# BNO055_Xplained_pro.net
KiCad netlist of a schematic drawn in Altium Designer
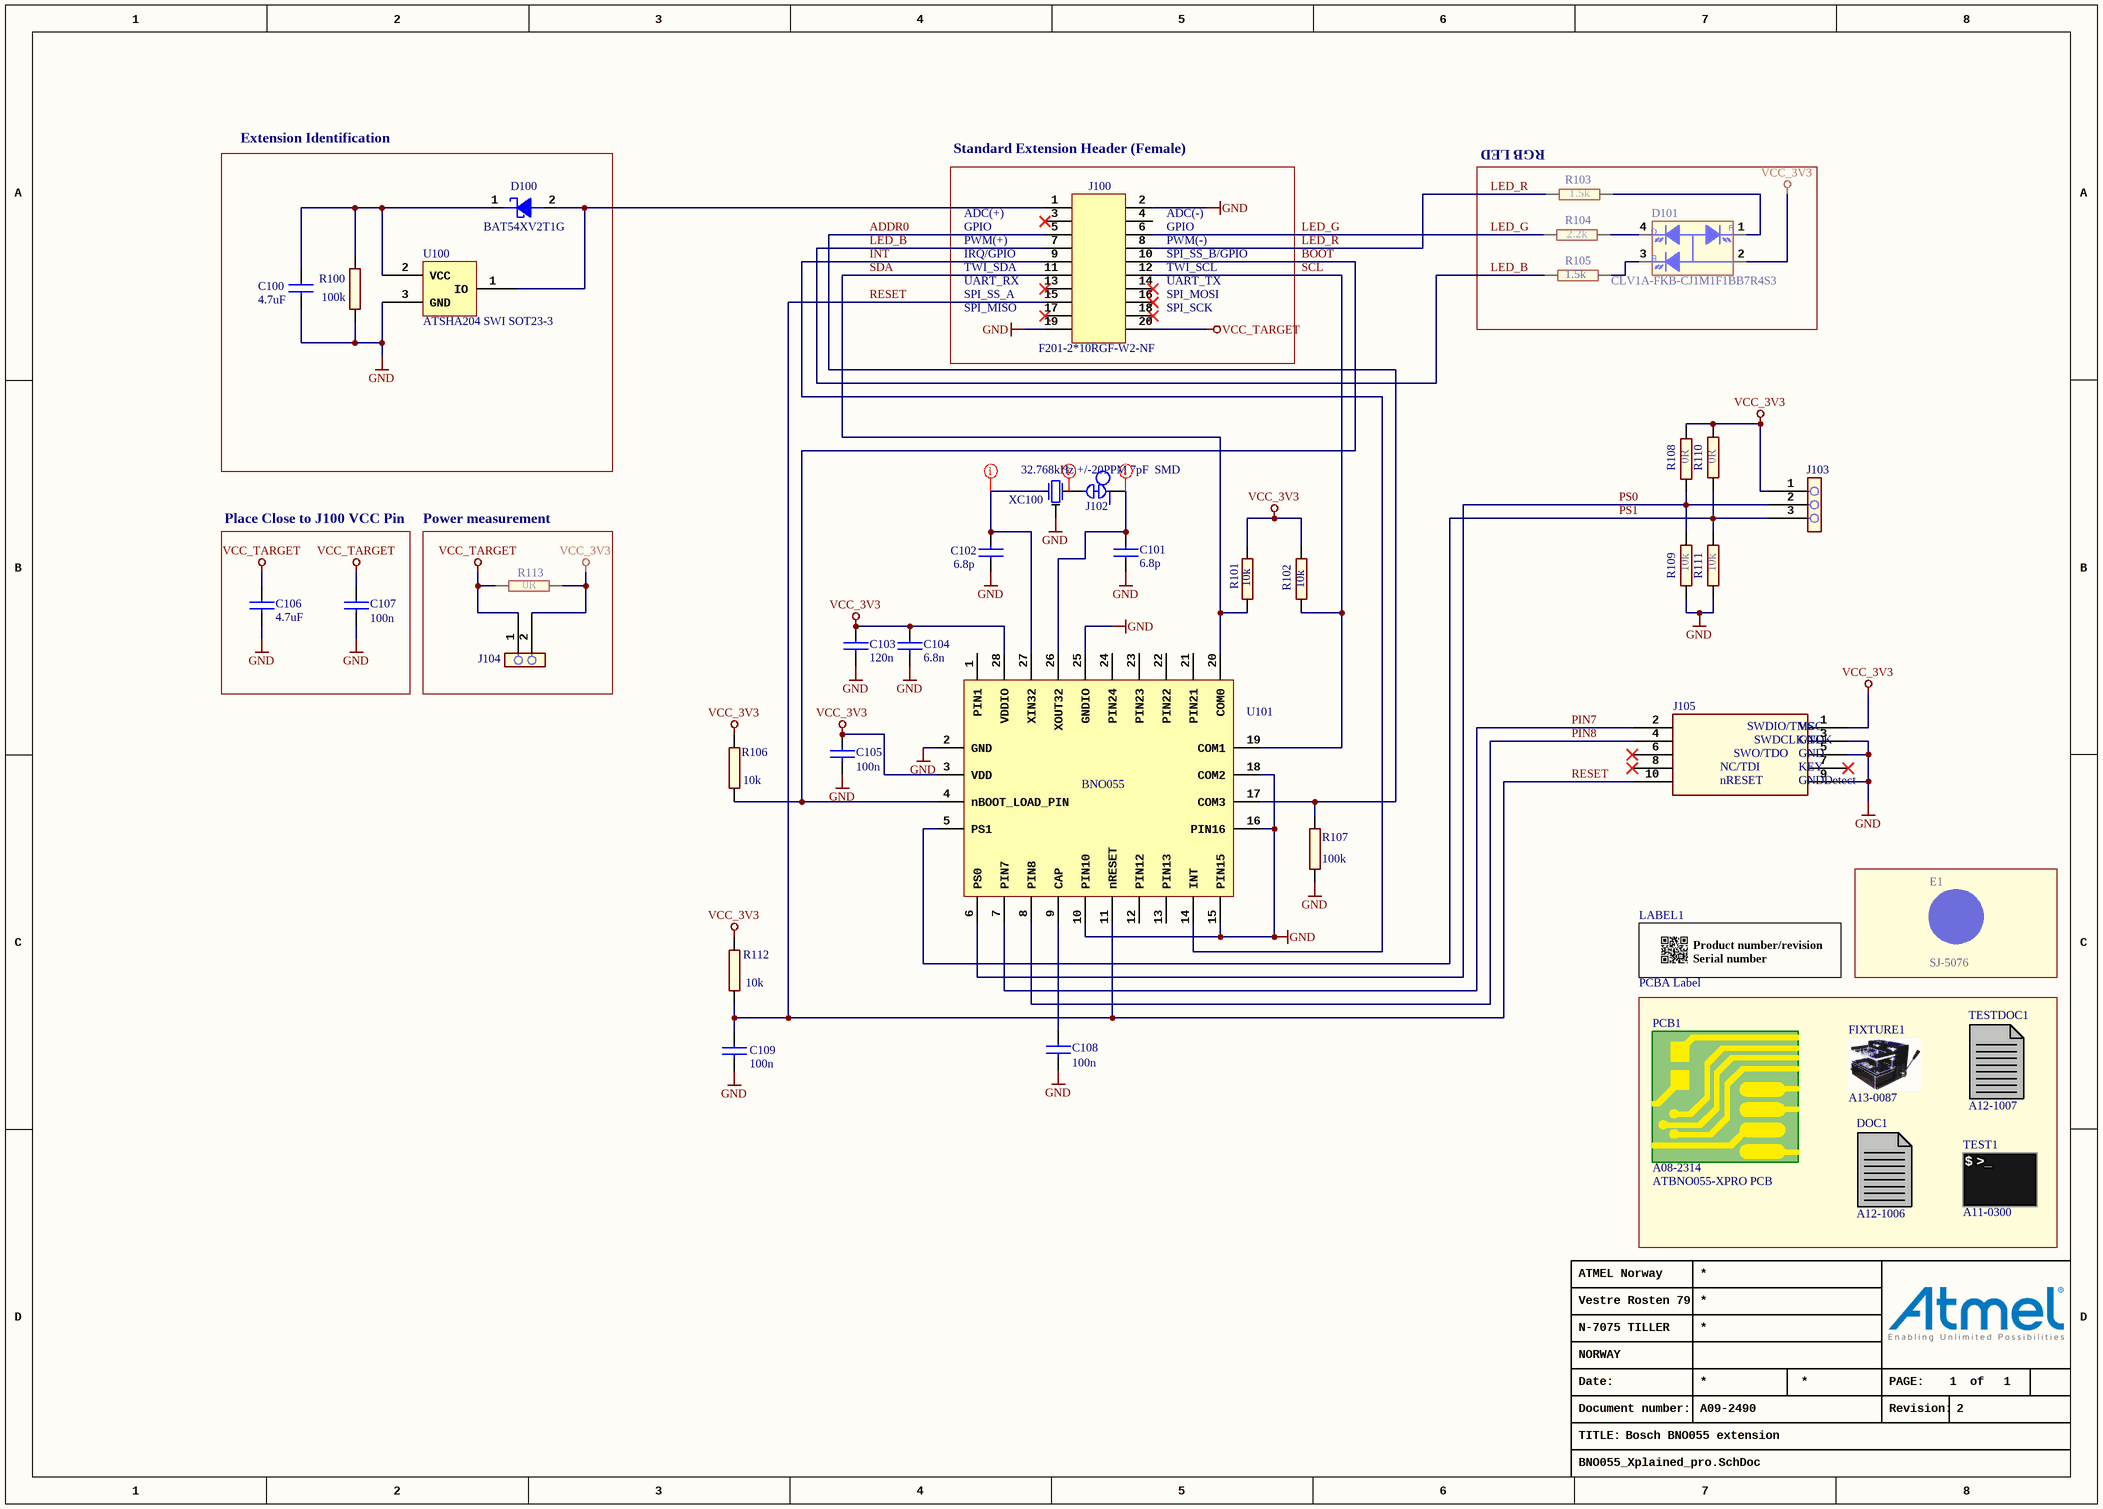
[diagram p0: BNO055_Xplained_pro.SchDoc]

(export (version "E")
  (design (tool "Eeschema 10.0.6"))
  (components
    (comp (ref "C100")
      (value "4.7uF")
      (footprint "AP1-00001")
      (description "Ceramic capacitor, SMD 0402, X5R, 6.3V, +/-20% (de33687)")
      (fields (field (name "TOLERANCE") "+-20%") (field (name "MANUFACTURER") "Murata"))
      (libsource (lib "AltiumDbLib") (part "CAP-NONPOL"))
    )
    (comp (ref "C101")
      (value "6.8p")
      (footprint "AP1-00001")
      (description "Ceramic capacitor, SMD 0402, NP0, 50V, +/-5%")
      (fields (field (name "TOLERANCE") "50V, +/-5%"))
      (libsource (lib "AltiumDbLib") (part "CAP-NONPOL"))
    )
    (comp (ref "C102")
      (value "6.8p")
      (footprint "AP1-00001")
      (description "Ceramic capacitor, SMD 0402, NP0, 50V, +/-5%")
      (fields (field (name "TOLERANCE") "50V, +/-5%"))
      (libsource (lib "AltiumDbLib") (part "CAP-NONPOL"))
    )
    (comp (ref "C103")
      (value "120n")
      (footprint "AP1-00002")
      (description "Ceramic capacitor, SMD 0603, X7R, 10V, Â±10%")
      (fields (field (name "MANUFACTURER") "AVX") (field (name "MPN") "0603ZC124KAT2A"))
      (libsource (lib "AltiumDbLib") (part "CAP-NONPOL"))
    )
    (comp (ref "C104")
      (value "6.8n")
      (footprint "AP1-00001")
      (description "Ceramic capacitor, SMD 0402, X7R, 25V, +/-10%")
      (fields (field (name "TOLERANCE") "25V, +/-10%"))
      (libsource (lib "AltiumDbLib") (part "CAP-NONPOL"))
    )
    (comp (ref "C105")
      (value "100n")
      (footprint "AP1-00053")
      (description "Ceramic capacitor, SMD 0402, X7R, 16V, +/-10%")
      (fields (field (name "TOLERANCE") "16V, +/-10%") (field (name "MANUFACTURER") "Kemet"))
      (libsource (lib "AltiumDbLib") (part "CAP-NONPOL"))
    )
    (comp (ref "C106")
      (value "4.7uF")
      (footprint "AP1-00001")
      (description "Ceramic capacitor, SMD 0402, X5R, 6.3V, +/-20% (de33687)")
      (fields (field (name "TOLERANCE") "+-20%") (field (name "MANUFACTURER") "Murata"))
      (libsource (lib "AltiumDbLib") (part "CAP-NONPOL"))
    )
    (comp (ref "C107")
      (value "100n")
      (footprint "AP1-00053")
      (description "Ceramic capacitor, SMD 0402, X7R, 16V, +/-10%")
      (fields (field (name "TOLERANCE") "16V, +/-10%") (field (name "MANUFACTURER") "Kemet"))
      (libsource (lib "AltiumDbLib") (part "CAP-NONPOL"))
    )
    (comp (ref "C108")
      (value "100n")
      (footprint "AP1-00053")
      (description "Ceramic capacitor, SMD 0402, X7R, 16V, +/-10%")
      (fields (field (name "TOLERANCE") "16V, +/-10%") (field (name "MANUFACTURER") "Kemet"))
      (libsource (lib "AltiumDbLib") (part "CAP-NONPOL"))
    )
    (comp (ref "C109")
      (value "100n")
      (footprint "AP1-00053")
      (description "Ceramic capacitor, SMD 0402, X7R, 16V, +/-10%")
      (fields (field (name "TOLERANCE") "16V, +/-10%") (field (name "MANUFACTURER") "Kemet"))
      (libsource (lib "AltiumDbLib") (part "CAP-NONPOL"))
    )
    (comp (ref "D100")
      (value "BAT54XV2T1G")
      (footprint "AP4-00036")
      (description "Schottky diode, If:200mA, Vf:0.35V, Vrrm:30V, SOD-523")
      (fields (field (name "MANUFACTURER") "ON Semiconductor") (field (name "Comment") "Farnell# 1615809"))
      (libsource (lib "AltiumDbLib") (part "SCHOTTKY_SMD_12"))
    )
    (comp (ref "D101")
      (value "CLV1A-FKB-CJ1M1F1BB7R4S3")
      (footprint "AP4-00104")
      (description "LED, RGB, diffuse lens, SMD PLCC-4")
      (fields (field (name "MANUFACTURER") "CREE") (field (name "Comment") "Farnell no: 1855553"))
      (libsource (lib "AltiumDbLib") (part "LED3_RGB1"))
    )
    (comp (ref "DOC1")
      (value "~")
      (description "ATBNO055-XPRO PCBA documentation")
      (fields (field (name "AN") "A12-1006"))
      (libsource (lib "AltiumDbLib") (part "DOCUMENTATION"))
    )
    (comp (ref "E1")
      (value "SJ-5076")
      (footprint "AP8-00192")
      (description "2.8mm adhesive feet,diam 8.0mm")
      (fields (field (name "MANUFACTURER") "3M"))
      (libsource (lib "AltiumDbLib") (part "RUBBER FEET"))
    )
    (comp (ref "FIXTURE1")
      (value "~")
      (description "Xplained PRO Extension board Jupiter Test Fixture")
      (fields (field (name "AN") "A13-0087") (field (name "MANUFACTURER") "ESCATEC"))
      (libsource (lib "AltiumDbLib") (part "JIG"))
    )
    (comp (ref "J100")
      (value "F201-2*10RGF-W2-NF")
      (footprint "AP8-00621")
      (description "2x10, female pin header receptable, right-angled, 2.54mm pitch, THM, Pin In Paste")
      (fields (field (name "MANUFACTURER") "Pro-data International Corp"))
      (libsource (lib "AltiumDbLib") (part "HEADER-2X10"))
    )
    (comp (ref "J102")
      (value "~")
      (footprint "AP8-00595")
      (description "Closed Link 0402")
      (libsource (lib "AltiumDbLib") (part "SMD-STRAP_CLOSED"))
    )
    (comp (ref "J103")
      (value "~")
      (footprint "AP8-00745")
      (description "1x3 pin header, 2.54mm pitch, Pin-in-Paste THM, 1mm hole")
      (fields (field (name "MANUFACTURER") "SAMTEC") (field (name "MPN") "HMTSW-103-23-F-S-237"))
      (libsource (lib "AltiumDbLib") (part "HEADER 1x3"))
    )
    (comp (ref "J104")
      (value "~")
      (footprint "AP8-00733")
      (description "1x2 pin header, 2.54mm pitch, Pin-in-Paste THM")
      (fields (field (name "MANUFACTURER") "SAMTEC") (field (name "MPN") "HMTSW-102-23-F-S-237"))
      (libsource (lib "AltiumDbLib") (part "HEADER 1x2"))
    )
    (comp (ref "J105")
      (value "~")
      (footprint "AP8-00257")
      (description "2x5 pin header, 1.27mm pitch, THM")
      (fields (field (name "MANUFACTURER") "Garry") (field (name "MPN") "176-2-010-0-T-XS0-0730"))
      (libsource (lib "AltiumDbLib") (part "HEADER 2x5"))
    )
    (comp (ref "LABEL1")
      (value "PCBA Label")
      (footprint "AP8-00317")
      (description "PCBA identification label PP Top White Gloss")
      (fields (field (name "MANUFACTURER") "ACT Logimark AS") (field (name "MPN") "505462"))
      (libsource (lib "AltiumDbLib") (part "PCBA_LABEL"))
    )
    (comp (ref "PCB1")
      (value "ATBNO055-XPRO PCB")
      (description "ATBNO055-XPRO PCB documentation")
      (fields (field (name "AN") "A08-2314"))
      (libsource (lib "AltiumDbLib") (part "PCB"))
    )
    (comp (ref "R100")
      (value "100k")
      (footprint "AP2-00000")
      (description "Thick film resistor, SMD 0402, 1/16W, 1%")
      (fields (field (name "TOLERANCE") "1 %"))
      (libsource (lib "") (part "R2_1"))
    )
    (comp (ref "R101")
      (value "10k")
      (footprint "AP2-00000")
      (description "Thick film resistor, SMD 0402, 1/16W, 1%")
      (fields (field (name "TOLERANCE") "1 %") (field (name "MANUFACTURER") "vishay"))
      (libsource (lib "") (part "R2_1"))
    )
    (comp (ref "R102")
      (value "10k")
      (footprint "AP2-00000")
      (description "Thick film resistor, SMD 0402, 1/16W, 1%")
      (fields (field (name "TOLERANCE") "1 %") (field (name "MANUFACTURER") "vishay"))
      (libsource (lib "") (part "R2_1"))
    )
    (comp (ref "R103")
      (value "1.5k")
      (footprint "AP2-00000")
      (description "Thick film resistor, SMD 0402, 1/16W, 1%")
      (fields (field (name "TOLERANCE") "1 %"))
      (libsource (lib "AltiumDbLib") (part "R2"))
    )
    (comp (ref "R104")
      (value "2.2k")
      (footprint "AP2-00000")
      (description "Thick film resistor, SMD 0402, 1/16W, 1%")
      (fields (field (name "TOLERANCE") "1 %"))
      (libsource (lib "AltiumDbLib") (part "R2"))
    )
    (comp (ref "R105")
      (value "1.5k")
      (footprint "AP2-00000")
      (description "Thick film resistor, SMD 0402, 1/16W, 1%")
      (fields (field (name "TOLERANCE") "1 %"))
      (libsource (lib "AltiumDbLib") (part "R2"))
    )
    (comp (ref "R106")
      (value "10k")
      (footprint "AP2-00000")
      (description "Thick film resistor, SMD 0402, 1/16W, 1%")
      (fields (field (name "TOLERANCE") "1 %") (field (name "MANUFACTURER") "vishay"))
      (libsource (lib "") (part "R2_1"))
    )
    (comp (ref "R107")
      (value "100k")
      (footprint "AP2-00000")
      (description "Thick film resistor, SMD 0402, 1/16W, 1%")
      (fields (field (name "TOLERANCE") "1 %"))
      (libsource (lib "") (part "R2_1"))
    )
    (comp (ref "R108")
      (value "0R")
      (footprint "AP2-00000")
      (description "RES 0.0 OHM 1/16W 0402 SMD")
      (fields (field (name "TOLERANCE") "1 %") (field (name "MANUFACTURER") "(n/a)"))
      (libsource (lib "") (part "R2_1"))
    )
    (comp (ref "R109")
      (value "10k")
      (footprint "AP2-00000")
      (description "Thick film resistor, SMD 0402, 1/16W, 1%")
      (fields (field (name "TOLERANCE") "1 %") (field (name "MANUFACTURER") "vishay"))
      (libsource (lib "AltiumDbLib") (part "R2"))
    )
    (comp (ref "R110")
      (value "0R")
      (footprint "AP2-00000")
      (description "RES 0.0 OHM 1/16W 0402 SMD")
      (fields (field (name "TOLERANCE") "1 %") (field (name "MANUFACTURER") "(n/a)"))
      (libsource (lib "") (part "R2_1"))
    )
    (comp (ref "R111")
      (value "10k")
      (footprint "AP2-00000")
      (description "Thick film resistor, SMD 0402, 1/16W, 1%")
      (fields (field (name "TOLERANCE") "1 %") (field (name "MANUFACTURER") "vishay"))
      (libsource (lib "AltiumDbLib") (part "R2"))
    )
    (comp (ref "R112")
      (value "10k")
      (footprint "AP2-00000")
      (description "Thick film resistor, SMD 0402, 1/16W, 1%")
      (fields (field (name "TOLERANCE") "1 %") (field (name "MANUFACTURER") "vishay"))
      (libsource (lib "AltiumDbLib") (part "R2"))
    )
    (comp (ref "R113")
      (value "0R")
      (footprint "AP2-00000")
      (description "RES 0.0 OHM 1/16W 0402 SMD")
      (fields (field (name "TOLERANCE") "1 %") (field (name "MANUFACTURER") "(n/a)"))
      (libsource (lib "") (part "R2_2"))
    )
    (comp (ref "TEST1")
      (value "~")
      (fields (field (name "AN") "A11-0300"))
      (libsource (lib "AltiumDbLib") (part "TEST"))
    )
    (comp (ref "TESTDOC1")
      (value "~")
      (description "BNO055-XPRO, A09-2490, test instruction,")
      (fields (field (name "AN") "A12-1007"))
      (libsource (lib "AltiumDbLib") (part "TESTDOC"))
    )
    (comp (ref "U100")
      (value "ATSHA204 SWI SOT23-3")
      (footprint "AP4-00018")
      (description "ATSHA204 with 1-wire interface and SOT23-3 package")
      (fields (field (name "MANUFACTURER") "ATMEL") (field (name "MPN") "ATSHA204A-STUCZ-T"))
      (libsource (lib "AltiumDbLib") (part "ATSHA204_SOT23"))
    )
    (comp (ref "U101")
      (value "BNO055")
      (footprint "AP6-00430")
      (description "Intelligent 9-Axis Absolute orientation sensor")
      (fields (field (name "MANUFACTURER") "Bosch Sensortech GmbH"))
      (libsource (lib "AltiumDbLib") (part "BNO055"))
    )
    (comp (ref "XC100")
      (value "32.768kHz +/-20PPM 7pF  SMD")
      (footprint "AP7-00044")
      (description "32k768 crystal, +-20ppm, CL=7pF, max ESR 60kOhm, SMD")
      (fields
        (field (name "MPN") "MS1V-T1K 32.768kHz 7pF +/-20PPM TA")
        (field (name "MANUFACTURER") "Micro Crystal")
      )
      (libsource (lib "AltiumDbLib") (part "CRYSTAL_2P_metal"))
    )
  )
  (nets
    (net (code "1") (name "/ADDR0") (class "Default")
      (node (ref "J100") (pin "5") (pintype "passive"))
      (node (ref "R107") (pin "2") (pinfunction "2_2") (pintype "passive"))
      (node (ref "U101") (pin "17") (pinfunction "COM3_17") (pintype "passive"))
    )
    (net (code "2") (name "/BOOT") (class "Default")
      (node (ref "J100") (pin "10") (pintype "passive"))
      (node (ref "R106") (pin "1") (pinfunction "1_1") (pintype "passive"))
      (node (ref "U101") (pin "4") (pinfunction "nBOOT_LOAD_PIN_4") (pintype "passive"))
    )
    (net (code "3") (name "/INT") (class "Default")
      (node (ref "J100") (pin "9") (pintype "passive"))
      (node (ref "U101") (pin "14") (pinfunction "INT_14") (pintype "passive"))
    )
    (net (code "4") (name "/LED_B") (class "Default")
      (node (ref "J100") (pin "7") (pintype "passive"))
      (node (ref "R105") (pin "2") (pinfunction "2_2") (pintype "passive"))
    )
    (net (code "5") (name "/LED_G") (class "Default")
      (node (ref "J100") (pin "6") (pintype "passive"))
      (node (ref "R104") (pin "2") (pinfunction "2_2") (pintype "passive"))
    )
    (net (code "6") (name "/LED_R") (class "Default")
      (node (ref "J100") (pin "8") (pintype "passive"))
      (node (ref "R103") (pin "2") (pinfunction "2_2") (pintype "passive"))
    )
    (net (code "7") (name "/PIN7") (class "Default")
      (node (ref "J105") (pin "2") (pinfunction "2_2") (pintype "passive"))
      (node (ref "U101") (pin "7") (pinfunction "PIN7_7") (pintype "passive"))
    )
    (net (code "8") (name "/PIN8") (class "Default")
      (node (ref "J105") (pin "4") (pinfunction "4_4") (pintype "passive"))
      (node (ref "U101") (pin "8") (pinfunction "PIN8_8") (pintype "passive"))
    )
    (net (code "9") (name "/PS0") (class "Default")
      (node (ref "J103") (pin "2") (pinfunction "2_2") (pintype "passive"))
      (node (ref "R108") (pin "1") (pinfunction "1_1") (pintype "passive"))
      (node (ref "R109") (pin "1") (pinfunction "1_1") (pintype "passive"))
      (node (ref "U101") (pin "6") (pinfunction "PS0_6") (pintype "passive"))
    )
    (net (code "10") (name "/PS1") (class "Default")
      (node (ref "J103") (pin "3") (pinfunction "3_3") (pintype "passive"))
      (node (ref "R110") (pin "1") (pinfunction "1_1") (pintype "passive"))
      (node (ref "R111") (pin "1") (pinfunction "1_1") (pintype "passive"))
      (node (ref "U101") (pin "5") (pinfunction "PS1_5") (pintype "passive"))
    )
    (net (code "11") (name "/RESET") (class "Default")
      (node (ref "C109") (pin "1") (pinfunction "1_1") (pintype "passive"))
      (node (ref "J100") (pin "15") (pintype "passive"))
      (node (ref "J105") (pin "10") (pinfunction "10_10") (pintype "passive"))
      (node (ref "R112") (pin "2") (pinfunction "2_2") (pintype "passive"))
      (node (ref "U101") (pin "11") (pinfunction "nRESET_11") (pintype "passive"))
    )
    (net (code "12") (name "/SCL") (class "Default")
      (node (ref "J100") (pin "12") (pintype "passive"))
      (node (ref "R102") (pin "1") (pinfunction "1_1") (pintype "passive"))
      (node (ref "U101") (pin "19") (pinfunction "COM1_19") (pintype "passive"))
    )
    (net (code "13") (name "/SDA") (class "Default")
      (node (ref "J100") (pin "11") (pintype "passive"))
      (node (ref "R101") (pin "1") (pinfunction "1_1") (pintype "passive"))
      (node (ref "U101") (pin "20") (pinfunction "COM0_20") (pintype "passive"))
    )
    (net (code "14") (name "GND") (class "Default")
      (node (ref "C100") (pin "2") (pinfunction "2_2") (pintype "passive"))
      (node (ref "C101") (pin "1") (pinfunction "1_1") (pintype "passive"))
      (node (ref "C102") (pin "1") (pinfunction "1_1") (pintype "passive"))
      (node (ref "C103") (pin "2") (pinfunction "2_2") (pintype "passive"))
      (node (ref "C104") (pin "2") (pinfunction "2_2") (pintype "passive"))
      (node (ref "C105") (pin "2") (pinfunction "2_2") (pintype "passive"))
      (node (ref "C106") (pin "2") (pinfunction "2_2") (pintype "passive"))
      (node (ref "C107") (pin "2") (pinfunction "2_2") (pintype "passive"))
      (node (ref "C108") (pin "2") (pinfunction "2_2") (pintype "passive"))
      (node (ref "C109") (pin "2") (pinfunction "2_2") (pintype "passive"))
      (node (ref "J100") (pin "19") (pintype "passive"))
      (node (ref "J100") (pin "2") (pintype "passive"))
      (node (ref "J105") (pin "3") (pinfunction "3_3") (pintype "passive"))
      (node (ref "J105") (pin "5") (pinfunction "5_5") (pintype "passive"))
      (node (ref "J105") (pin "9") (pinfunction "9_9") (pintype "passive"))
      (node (ref "R100") (pin "1") (pinfunction "1_1") (pintype "passive"))
      (node (ref "R107") (pin "1") (pinfunction "1_1") (pintype "passive"))
      (node (ref "R109") (pin "2") (pinfunction "2_2") (pintype "passive"))
      (node (ref "R111") (pin "2") (pinfunction "2_2") (pintype "passive"))
      (node (ref "U100") (pin "3") (pinfunction "GND_3") (pintype "passive"))
      (node (ref "U101") (pin "10") (pinfunction "PIN10_10") (pintype "passive"))
      (node (ref "U101") (pin "15") (pinfunction "PIN15_15") (pintype "passive"))
      (node (ref "U101") (pin "16") (pinfunction "PIN16_16") (pintype "passive"))
      (node (ref "U101") (pin "18") (pinfunction "COM2_18") (pintype "passive"))
      (node (ref "U101") (pin "2") (pinfunction "GND_2") (pintype "passive"))
      (node (ref "U101") (pin "25") (pinfunction "GNDIO_25") (pintype "passive"))
      (node (ref "XC100") (pin "3") (pinfunction "3_3") (pintype "passive"))
    )
    (net (code "15") (name "Net-(D100-ANODE)") (class "Default")
      (node (ref "D100") (pin "2") (pinfunction "ANODE_2") (pintype "passive"))
      (node (ref "J100") (pin "1") (pintype "passive"))
      (node (ref "U100") (pin "1") (pinfunction "IO_1") (pintype "passive"))
    )
    (net (code "16") (name "Net-(D100-CATHODE)") (class "Default")
      (node (ref "C100") (pin "1") (pinfunction "1_1") (pintype "passive"))
      (node (ref "D100") (pin "1") (pinfunction "CATHODE_1") (pintype "passive"))
      (node (ref "R100") (pin "2") (pinfunction "2_2") (pintype "passive"))
      (node (ref "U100") (pin "2") (pinfunction "VCC_2") (pintype "passive"))
    )
    (net (code "17") (name "Net-(D101-CATHODE1)") (class "Default")
      (node (ref "D101") (pin "1") (pinfunction "CATHODE1_1") (pintype "passive"))
      (node (ref "R103") (pin "1") (pinfunction "1_1") (pintype "passive"))
    )
    (net (code "18") (name "Net-(D101-CATHODE2)") (class "Default")
      (node (ref "D101") (pin "3") (pinfunction "CATHODE2_3") (pintype "passive"))
      (node (ref "R105") (pin "1") (pinfunction "1_1") (pintype "passive"))
    )
    (net (code "19") (name "Net-(D101-CATHODE3)") (class "Default")
      (node (ref "D101") (pin "4") (pinfunction "CATHODE3_4") (pintype "passive"))
      (node (ref "R104") (pin "1") (pinfunction "1_1") (pintype "passive"))
    )
    (net (code "20") (name "Net-(J102-Pad2)") (class "Default")
      (node (ref "J102") (pin "2") (pinfunction "2_2") (pintype "passive"))
      (node (ref "XC100") (pin "2") (pinfunction "2_2") (pintype "passive"))
    )
    (net (code "21") (name "Net-(U101-CAP)") (class "Default")
      (node (ref "C108") (pin "1") (pinfunction "1_1") (pintype "passive"))
      (node (ref "U101") (pin "9") (pinfunction "CAP_9") (pintype "passive"))
    )
    (net (code "22") (name "Net-(U101-XIN32)") (class "Default")
      (node (ref "C102") (pin "2") (pinfunction "2_2") (pintype "passive"))
      (node (ref "U101") (pin "27") (pinfunction "XIN32_27") (pintype "passive"))
      (node (ref "XC100") (pin "1") (pinfunction "1_1") (pintype "passive"))
    )
    (net (code "23") (name "Net-(U101-XOUT32)") (class "Default")
      (node (ref "C101") (pin "2") (pinfunction "2_2") (pintype "passive"))
      (node (ref "J102") (pin "1") (pinfunction "1_1") (pintype "passive"))
      (node (ref "U101") (pin "26") (pinfunction "XOUT32_26") (pintype "passive"))
    )
    (net (code "24") (name "VCC_3V3") (class "Default")
      (node (ref "C103") (pin "1") (pinfunction "1_1") (pintype "passive"))
      (node (ref "C104") (pin "1") (pinfunction "1_1") (pintype "passive"))
      (node (ref "C105") (pin "1") (pinfunction "1_1") (pintype "passive"))
      (node (ref "D101") (pin "2") (pinfunction "COMMON_ANODE_2") (pintype "passive"))
      (node (ref "J103") (pin "1") (pinfunction "1_1") (pintype "passive"))
      (node (ref "J104") (pin "2") (pinfunction "2_2") (pintype "passive"))
      (node (ref "J105") (pin "1") (pinfunction "1_1") (pintype "passive"))
      (node (ref "R101") (pin "2") (pinfunction "2_2") (pintype "passive"))
      (node (ref "R102") (pin "2") (pinfunction "2_2") (pintype "passive"))
      (node (ref "R106") (pin "2") (pinfunction "2_2") (pintype "passive"))
      (node (ref "R108") (pin "2") (pinfunction "2_2") (pintype "passive"))
      (node (ref "R110") (pin "2") (pinfunction "2_2") (pintype "passive"))
      (node (ref "R112") (pin "1") (pinfunction "1_1") (pintype "passive"))
      (node (ref "R113") (pin "1") (pinfunction "1_1") (pintype "passive"))
      (node (ref "U101") (pin "28") (pinfunction "VDDIO_28") (pintype "passive"))
      (node (ref "U101") (pin "3") (pinfunction "VDD_3") (pintype "passive"))
    )
    (net (code "25") (name "VCC_TARGET") (class "Default")
      (node (ref "C106") (pin "1") (pinfunction "1_1") (pintype "passive"))
      (node (ref "C107") (pin "1") (pinfunction "1_1") (pintype "passive"))
      (node (ref "J100") (pin "20") (pintype "passive"))
      (node (ref "J104") (pin "1") (pinfunction "1_1") (pintype "passive"))
      (node (ref "R113") (pin "2") (pinfunction "2_2") (pintype "passive"))
    )
    (net (code "26") (name "unconnected-(E1-FIDUCIAL-Pad1)") (class "Default")
      (node (ref "E1") (pin "1") (pinfunction "FIDUCIAL_1") (pintype "passive"))
    )
    (net (code "27") (name "unconnected-(J100-Pad3)") (class "Default")
      (node (ref "J100") (pin "3") (pintype "passive+no_connect"))
    )
    (net (code "28") (name "unconnected-(J100-Pad4)") (class "Default")
      (node (ref "J100") (pin "4") (pintype "passive"))
    )
    (net (code "29") (name "unconnected-(J100-Pad13)") (class "Default")
      (node (ref "J100") (pin "13") (pintype "passive+no_connect"))
    )
    (net (code "30") (name "unconnected-(J100-Pad14)") (class "Default")
      (node (ref "J100") (pin "14") (pintype "passive+no_connect"))
    )
    (net (code "31") (name "unconnected-(J100-Pad16)") (class "Default")
      (node (ref "J100") (pin "16") (pintype "passive+no_connect"))
    )
    (net (code "32") (name "unconnected-(J100-Pad17)") (class "Default")
      (node (ref "J100") (pin "17") (pintype "passive+no_connect"))
    )
    (net (code "33") (name "unconnected-(J100-Pad18)") (class "Default")
      (node (ref "J100") (pin "18") (pintype "passive+no_connect"))
    )
    (net (code "34") (name "unconnected-(J105-Pad6)") (class "Default")
      (node (ref "J105") (pin "6") (pinfunction "6_6") (pintype "passive+no_connect"))
    )
    (net (code "35") (name "unconnected-(J105-Pad7)") (class "Default")
      (node (ref "J105") (pin "7") (pinfunction "7_7") (pintype "passive+no_connect"))
    )
    (net (code "36") (name "unconnected-(J105-Pad8)") (class "Default")
      (node (ref "J105") (pin "8") (pinfunction "8_8") (pintype "passive+no_connect"))
    )
    (net (code "37") (name "unconnected-(U101-PIN1-Pad1)") (class "Default")
      (node (ref "U101") (pin "1") (pinfunction "PIN1_1") (pintype "passive"))
    )
    (net (code "38") (name "unconnected-(U101-PIN12-Pad12)") (class "Default")
      (node (ref "U101") (pin "12") (pinfunction "PIN12_12") (pintype "passive"))
    )
    (net (code "39") (name "unconnected-(U101-PIN13-Pad13)") (class "Default")
      (node (ref "U101") (pin "13") (pinfunction "PIN13_13") (pintype "passive"))
    )
    (net (code "40") (name "unconnected-(U101-PIN21-Pad21)") (class "Default")
      (node (ref "U101") (pin "21") (pinfunction "PIN21_21") (pintype "passive"))
    )
    (net (code "41") (name "unconnected-(U101-PIN22-Pad22)") (class "Default")
      (node (ref "U101") (pin "22") (pinfunction "PIN22_22") (pintype "passive"))
    )
    (net (code "42") (name "unconnected-(U101-PIN23-Pad23)") (class "Default")
      (node (ref "U101") (pin "23") (pinfunction "PIN23_23") (pintype "passive"))
    )
    (net (code "43") (name "unconnected-(U101-PIN24-Pad24)") (class "Default")
      (node (ref "U101") (pin "24") (pinfunction "PIN24_24") (pintype "passive"))
    )
  )
)
